# whypod.net
KiCad netlist of a schematic drawn in EAGLE
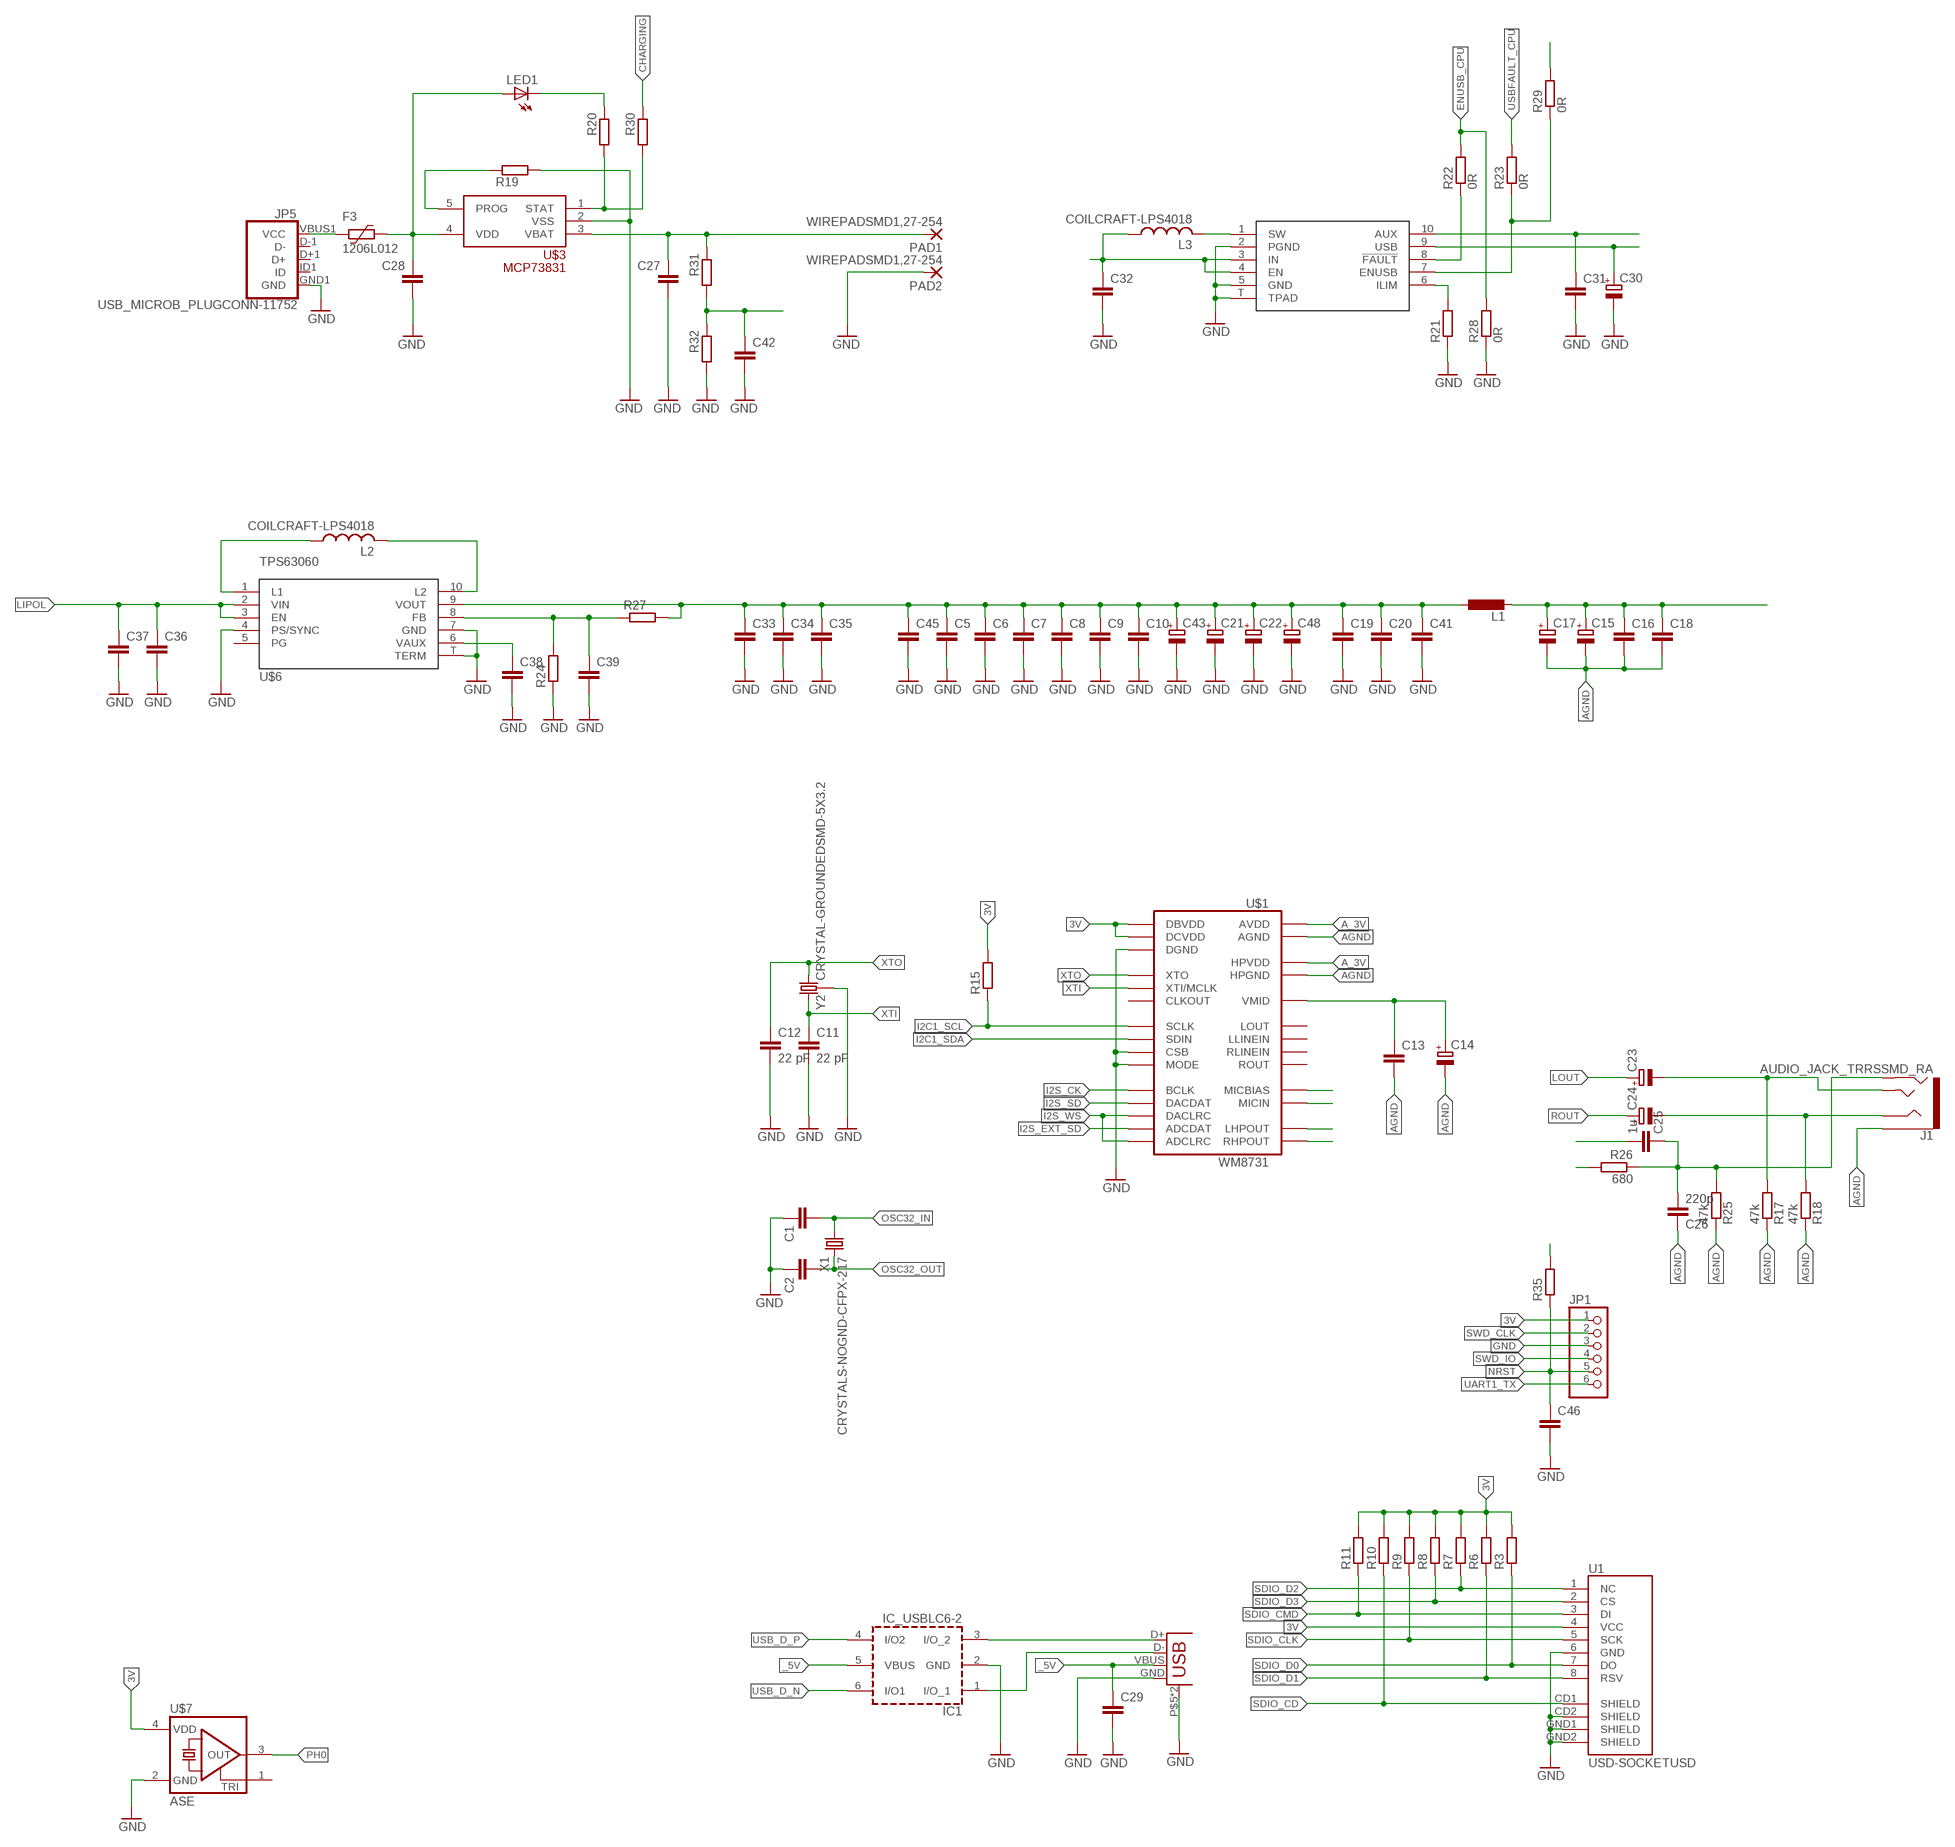
[diagram p0: schematic, sheet 1, part 1 of 2]
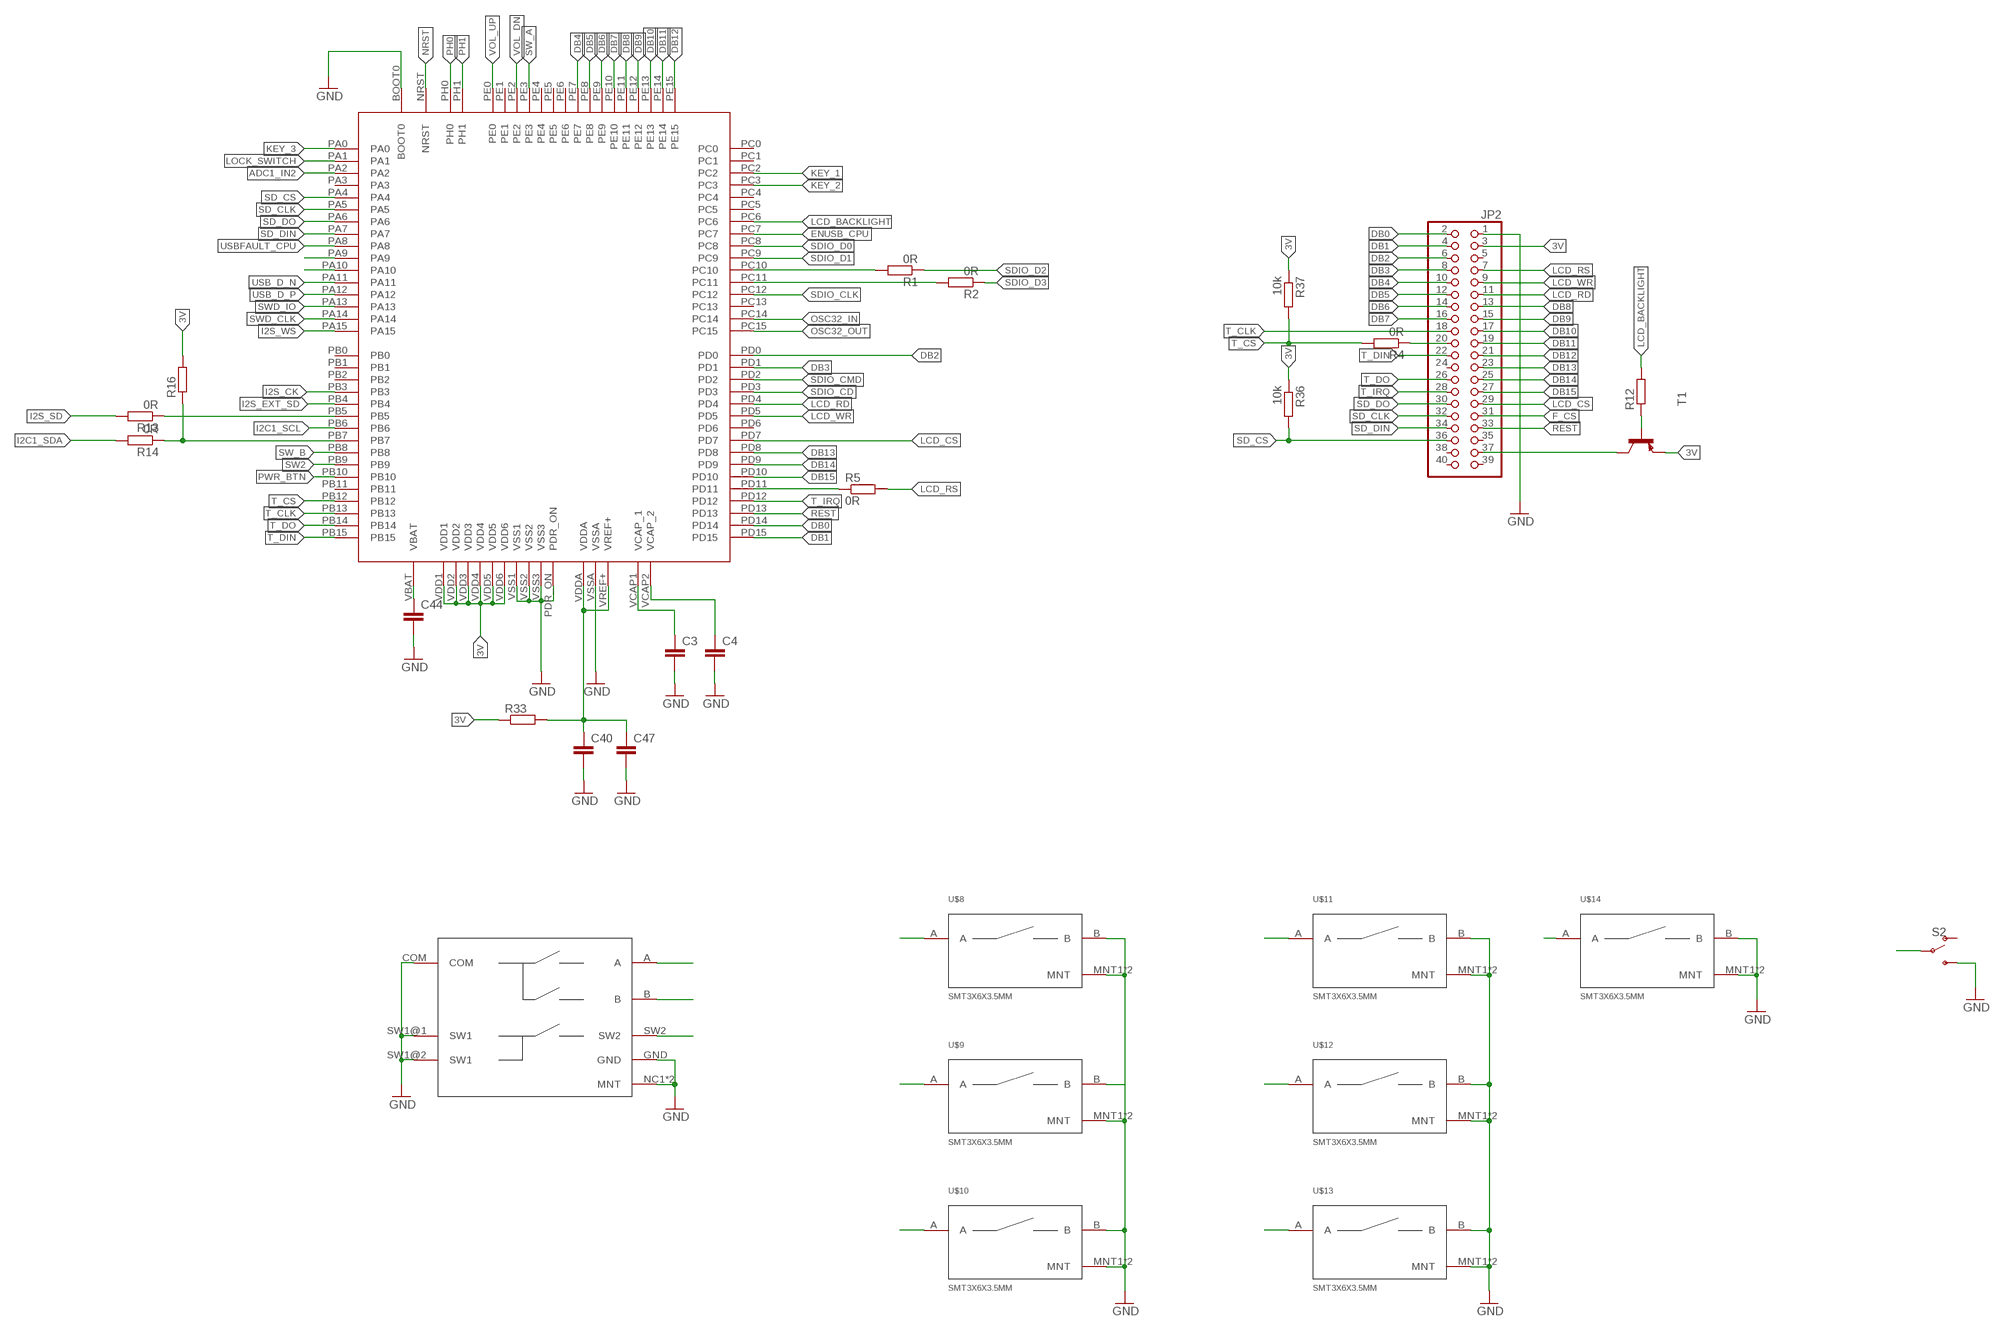
[diagram p1: schematic, sheet 1, part 2 of 2]

(export (version "E")
  (design (tool "Eeschema 10.0.6"))
  (components
    (comp (ref "C1")
      (value "C-EUC0603")
      (footprint "eagle-import:C0603")
      (libsource (lib "eagle-import") (part "C-EUC0603"))
    )
    (comp (ref "C2")
      (value "C-EUC0603")
      (footprint "eagle-import:C0603")
      (libsource (lib "eagle-import") (part "C-EUC0603"))
    )
    (comp (ref "C3")
      (value "C-EUC0603")
      (footprint "eagle-import:C0603")
      (libsource (lib "eagle-import") (part "C-EUC0603"))
    )
    (comp (ref "C4")
      (value "C-EUC0603")
      (footprint "eagle-import:C0603")
      (libsource (lib "eagle-import") (part "C-EUC0603"))
    )
    (comp (ref "C5")
      (value "C-EUC0603")
      (footprint "eagle-import:C0603")
      (libsource (lib "eagle-import") (part "C-EUC0603"))
    )
    (comp (ref "C6")
      (value "C-EUC0603")
      (footprint "eagle-import:C0603")
      (libsource (lib "eagle-import") (part "C-EUC0603"))
    )
    (comp (ref "C7")
      (value "C-EUC0402")
      (footprint "eagle-import:C0402")
      (libsource (lib "eagle-import") (part "C-EUC0402"))
    )
    (comp (ref "C8")
      (value "C-EUC0603")
      (footprint "eagle-import:C0603")
      (libsource (lib "eagle-import") (part "C-EUC0603"))
    )
    (comp (ref "C9")
      (value "C-EUC0603")
      (footprint "eagle-import:C0603")
      (libsource (lib "eagle-import") (part "C-EUC0603"))
    )
    (comp (ref "C10")
      (value "C-EUC0603")
      (footprint "eagle-import:C0603")
      (libsource (lib "eagle-import") (part "C-EUC0603"))
    )
    (comp (ref "C11")
      (value "22 pF")
      (footprint "eagle-import:C0603")
      (libsource (lib "eagle-import") (part "C-EUC0603"))
    )
    (comp (ref "C12")
      (value "22 pF")
      (footprint "eagle-import:C0603")
      (libsource (lib "eagle-import") (part "C-EUC0603"))
    )
    (comp (ref "C13")
      (value "C-EUC0603")
      (footprint "eagle-import:C0603")
      (libsource (lib "eagle-import") (part "C-EUC0603"))
    )
    (comp (ref "C14")
      (value "CPOL-EUSMCA")
      (footprint "eagle-import:SMC_A")
      (libsource (lib "eagle-import") (part "CPOL-EUSMCA"))
    )
    (comp (ref "C15")
      (value "CPOL-EUSMCA")
      (footprint "eagle-import:SMC_A")
      (libsource (lib "eagle-import") (part "CPOL-EUSMCA"))
    )
    (comp (ref "C16")
      (value "C-EUC0603")
      (footprint "eagle-import:C0603")
      (libsource (lib "eagle-import") (part "C-EUC0603"))
    )
    (comp (ref "C17")
      (value "CPOL-EUSMCA")
      (footprint "eagle-import:SMC_A")
      (libsource (lib "eagle-import") (part "CPOL-EUSMCA"))
    )
    (comp (ref "C18")
      (value "C-EUC0603")
      (footprint "eagle-import:C0603")
      (libsource (lib "eagle-import") (part "C-EUC0603"))
    )
    (comp (ref "C19")
      (value "C-EUC0603")
      (footprint "eagle-import:C0603")
      (libsource (lib "eagle-import") (part "C-EUC0603"))
    )
    (comp (ref "C20")
      (value "C-EUC0603")
      (footprint "eagle-import:C0603")
      (libsource (lib "eagle-import") (part "C-EUC0603"))
    )
    (comp (ref "C21")
      (value "CPOL-EUSMCA")
      (footprint "eagle-import:SMC_A")
      (libsource (lib "eagle-import") (part "CPOL-EUSMCA"))
    )
    (comp (ref "C22")
      (value "CPOL-EUSMCA")
      (footprint "eagle-import:SMC_A")
      (libsource (lib "eagle-import") (part "CPOL-EUSMCA"))
    )
    (comp (ref "C23")
      (value "CPOL-EUSMCE")
      (footprint "eagle-import:SMC_E")
      (libsource (lib "eagle-import") (part "CPOL-EUSMCE"))
    )
    (comp (ref "C24")
      (value "CPOL-EUSMCE")
      (footprint "eagle-import:SMC_E")
      (libsource (lib "eagle-import") (part "CPOL-EUSMCE"))
    )
    (comp (ref "C25")
      (value "1u")
      (footprint "eagle-import:C0603")
      (libsource (lib "eagle-import") (part "C-EUC0603"))
    )
    (comp (ref "C26")
      (value "220p")
      (footprint "eagle-import:C0603")
      (libsource (lib "eagle-import") (part "C-EUC0603"))
    )
    (comp (ref "C27")
      (value "C-EUC0603")
      (footprint "eagle-import:C0603")
      (libsource (lib "eagle-import") (part "C-EUC0603"))
    )
    (comp (ref "C28")
      (value "C-EUC0603")
      (footprint "eagle-import:C0603")
      (libsource (lib "eagle-import") (part "C-EUC0603"))
    )
    (comp (ref "C29")
      (value "C-EUC0603")
      (footprint "eagle-import:C0603")
      (libsource (lib "eagle-import") (part "C-EUC0603"))
    )
    (comp (ref "C30")
      (value "CPOL-EUSMCD")
      (footprint "eagle-import:SMC_D")
      (libsource (lib "eagle-import") (part "CPOL-EUSMCD"))
    )
    (comp (ref "C31")
      (value "C-EUC0603")
      (footprint "eagle-import:C0603")
      (libsource (lib "eagle-import") (part "C-EUC0603"))
    )
    (comp (ref "C32")
      (value "C-EUC0603")
      (footprint "eagle-import:C0603")
      (libsource (lib "eagle-import") (part "C-EUC0603"))
    )
    (comp (ref "C33")
      (value "C-EUC0805")
      (footprint "eagle-import:C0805")
      (libsource (lib "eagle-import") (part "C-EUC0805"))
    )
    (comp (ref "C34")
      (value "C-EUC0805")
      (footprint "eagle-import:C0805")
      (libsource (lib "eagle-import") (part "C-EUC0805"))
    )
    (comp (ref "C35")
      (value "C-EUC0805")
      (footprint "eagle-import:C0805")
      (libsource (lib "eagle-import") (part "C-EUC0805"))
    )
    (comp (ref "C36")
      (value "C-EUC0805")
      (footprint "eagle-import:C0805")
      (libsource (lib "eagle-import") (part "C-EUC0805"))
    )
    (comp (ref "C37")
      (value "C-EUC0805")
      (footprint "eagle-import:C0805")
      (libsource (lib "eagle-import") (part "C-EUC0805"))
    )
    (comp (ref "C38")
      (value "C-EUC0603")
      (footprint "eagle-import:C0603")
      (libsource (lib "eagle-import") (part "C-EUC0603"))
    )
    (comp (ref "C39")
      (value "C-EUC0402")
      (footprint "eagle-import:C0402")
      (libsource (lib "eagle-import") (part "C-EUC0402"))
    )
    (comp (ref "C40")
      (value "C-EUC0402")
      (footprint "eagle-import:C0402")
      (libsource (lib "eagle-import") (part "C-EUC0402"))
    )
    (comp (ref "C41")
      (value "C-EUC0402")
      (footprint "eagle-import:C0402")
      (libsource (lib "eagle-import") (part "C-EUC0402"))
    )
    (comp (ref "C42")
      (value "C-EUC0603")
      (footprint "eagle-import:C0603")
      (libsource (lib "eagle-import") (part "C-EUC0603"))
    )
    (comp (ref "C43")
      (value "CPOL-EUSMCA")
      (footprint "eagle-import:SMC_A")
      (libsource (lib "eagle-import") (part "CPOL-EUSMCA"))
    )
    (comp (ref "C44")
      (value "C-EUC0402")
      (footprint "eagle-import:C0402")
      (libsource (lib "eagle-import") (part "C-EUC0402"))
    )
    (comp (ref "C45")
      (value "C-EUC0402")
      (footprint "eagle-import:C0402")
      (libsource (lib "eagle-import") (part "C-EUC0402"))
    )
    (comp (ref "C46")
      (value "C-EUC0603")
      (footprint "eagle-import:C0603")
      (libsource (lib "eagle-import") (part "C-EUC0603"))
    )
    (comp (ref "C47")
      (value "C-EUC0603")
      (footprint "eagle-import:C0603")
      (libsource (lib "eagle-import") (part "C-EUC0603"))
    )
    (comp (ref "C48")
      (value "CPOL-EUSMCA")
      (footprint "eagle-import:SMC_A")
      (libsource (lib "eagle-import") (part "CPOL-EUSMCA"))
    )
    (comp (ref "F3")
      (value "1206L012")
      (footprint "eagle-import:1206L")
      (fields (field (name "MF") "Littelfuse"))
      (libsource (lib "eagle-import") (part "?1206L012"))
    )
    (comp (ref "IC1")
      (value "IC_USBLC6-2")
      (footprint "eagle-import:SOT-23-6L")
      (libsource (lib "eagle-import") (part "IC_USBLC6-2"))
    )
    (comp (ref "J1")
      (value "AUDIO_JACK_TRRSSMD_RA")
      (footprint "eagle-import:AUDIO_JACK_3.5MM_TRRS_SMD_RA")
      (libsource (lib "eagle-import") (part "AUDIO_JACK_TRRSSMD_RA"))
    )
    (comp (ref "JP1")
      (value "PINHD-1X06_2.54-SMD-90°")
      (footprint "eagle-import:1X06SMD_90")
      (libsource (lib "eagle-import") (part "PINHD-1X06_2.54-SMD-90°"))
    )
    (comp (ref "JP2")
      (value "PINHD-2X20_2.54-SMD")
      (footprint "eagle-import:2X20SMD")
      (libsource (lib "eagle-import") (part "PINHD-2X20_2.54-SMD"))
    )
    (comp (ref "JP5")
      (value "USB_MICROB_PLUGCONN-11752")
      (footprint "eagle-import:USB-B-MICRO-SMD_V03")
      (libsource (lib "eagle-import") (part "USB_MICROB_PLUGCONN-11752"))
    )
    (comp (ref "L1")
      (value "L-EUL3225M")
      (footprint "eagle-import:L3225M")
      (libsource (lib "eagle-import") (part "L-EUL3225M"))
    )
    (comp (ref "L2")
      (value "COILCRAFT-LPS4018")
      (footprint "eagle-import:LPS4018")
      (libsource (lib "eagle-import") (part "COILCRAFT-LPS4018"))
    )
    (comp (ref "L3")
      (value "COILCRAFT-LPS4018")
      (footprint "eagle-import:LPS4018")
      (libsource (lib "eagle-import") (part "COILCRAFT-LPS4018"))
    )
    (comp (ref "LED1")
      (value "LEDCHIP-LED0603")
      (footprint "eagle-import:CHIP-LED0603")
      (libsource (lib "eagle-import") (part "LEDCHIP-LED0603"))
    )
    (comp (ref "PAD1")
      (value "WIREPADSMD1,27-254")
      (footprint "eagle-import:SMD1,27-2,54")
      (libsource (lib "eagle-import") (part "WIREPADSMD1,27-254"))
    )
    (comp (ref "PAD2")
      (value "WIREPADSMD1,27-254")
      (footprint "eagle-import:SMD1,27-2,54")
      (libsource (lib "eagle-import") (part "WIREPADSMD1,27-254"))
    )
    (comp (ref "R1")
      (value "0R")
      (footprint "eagle-import:R0603")
      (libsource (lib "eagle-import") (part "R-EU_R0603"))
    )
    (comp (ref "R2")
      (value "0R")
      (footprint "eagle-import:R0603")
      (libsource (lib "eagle-import") (part "R-EU_R0603"))
    )
    (comp (ref "R3")
      (value "R-EU_R0603")
      (footprint "eagle-import:R0603")
      (libsource (lib "eagle-import") (part "R-EU_R0603"))
    )
    (comp (ref "R4")
      (value "0R")
      (footprint "eagle-import:R0603")
      (libsource (lib "eagle-import") (part "R-EU_R0603"))
    )
    (comp (ref "R5")
      (value "0R")
      (footprint "eagle-import:R0603")
      (libsource (lib "eagle-import") (part "R-EU_R0603"))
    )
    (comp (ref "R6")
      (value "R-EU_R0603")
      (footprint "eagle-import:R0603")
      (libsource (lib "eagle-import") (part "R-EU_R0603"))
    )
    (comp (ref "R7")
      (value "R-EU_R0402")
      (footprint "eagle-import:R0402")
      (libsource (lib "eagle-import") (part "R-EU_R0402"))
    )
    (comp (ref "R8")
      (value "R-EU_R0603")
      (footprint "eagle-import:R0603")
      (libsource (lib "eagle-import") (part "R-EU_R0603"))
    )
    (comp (ref "R9")
      (value "R-EU_R0402")
      (footprint "eagle-import:R0402")
      (libsource (lib "eagle-import") (part "R-EU_R0402"))
    )
    (comp (ref "R10")
      (value "R-EU_R0603")
      (footprint "eagle-import:R0603")
      (libsource (lib "eagle-import") (part "R-EU_R0603"))
    )
    (comp (ref "R11")
      (value "R-EU_R0603")
      (footprint "eagle-import:R0603")
      (libsource (lib "eagle-import") (part "R-EU_R0603"))
    )
    (comp (ref "R12")
      (value "R-EU_R0402")
      (footprint "eagle-import:R0402")
      (libsource (lib "eagle-import") (part "R-EU_R0402"))
    )
    (comp (ref "R13")
      (value "0R")
      (footprint "eagle-import:R0603")
      (libsource (lib "eagle-import") (part "R-EU_R0603"))
    )
    (comp (ref "R14")
      (value "0R")
      (footprint "eagle-import:R0603")
      (libsource (lib "eagle-import") (part "R-EU_R0603"))
    )
    (comp (ref "R15")
      (value "R-EU_R0603")
      (footprint "eagle-import:R0603")
      (libsource (lib "eagle-import") (part "R-EU_R0603"))
    )
    (comp (ref "R16")
      (value "R-EU_R0402")
      (footprint "eagle-import:R0402")
      (libsource (lib "eagle-import") (part "R-EU_R0402"))
    )
    (comp (ref "R17")
      (value "47k")
      (footprint "eagle-import:R0603")
      (libsource (lib "eagle-import") (part "R-EU_R0603"))
    )
    (comp (ref "R18")
      (value "47k")
      (footprint "eagle-import:R0603")
      (libsource (lib "eagle-import") (part "R-EU_R0603"))
    )
    (comp (ref "R19")
      (value "R-EU_R0603")
      (footprint "eagle-import:R0603")
      (libsource (lib "eagle-import") (part "R-EU_R0603"))
    )
    (comp (ref "R20")
      (value "R-EU_R0603")
      (footprint "eagle-import:R0603")
      (libsource (lib "eagle-import") (part "R-EU_R0603"))
    )
    (comp (ref "R21")
      (value "R-EU_R0603")
      (footprint "eagle-import:R0603")
      (libsource (lib "eagle-import") (part "R-EU_R0603"))
    )
    (comp (ref "R22")
      (value "0R")
      (footprint "eagle-import:R0603")
      (libsource (lib "eagle-import") (part "R-EU_R0603"))
    )
    (comp (ref "R23")
      (value "0R")
      (footprint "eagle-import:R0603")
      (libsource (lib "eagle-import") (part "R-EU_R0603"))
    )
    (comp (ref "R24")
      (value "R-EU_R0402")
      (footprint "eagle-import:R0402")
      (libsource (lib "eagle-import") (part "R-EU_R0402"))
    )
    (comp (ref "R25")
      (value "47k")
      (footprint "eagle-import:R0603")
      (libsource (lib "eagle-import") (part "R-EU_R0603"))
    )
    (comp (ref "R26")
      (value "680")
      (footprint "eagle-import:R0603")
      (libsource (lib "eagle-import") (part "R-EU_R0603"))
    )
    (comp (ref "R27")
      (value "R-EU_R0402")
      (footprint "eagle-import:R0402")
      (libsource (lib "eagle-import") (part "R-EU_R0402"))
    )
    (comp (ref "R28")
      (value "0R")
      (footprint "eagle-import:R0603")
      (libsource (lib "eagle-import") (part "R-EU_R0603"))
    )
    (comp (ref "R29")
      (value "0R")
      (footprint "eagle-import:R0603")
      (libsource (lib "eagle-import") (part "R-EU_R0603"))
    )
    (comp (ref "R30")
      (value "R-EU_R0603")
      (footprint "eagle-import:R0603")
      (libsource (lib "eagle-import") (part "R-EU_R0603"))
    )
    (comp (ref "R31")
      (value "R-EU_R0603")
      (footprint "eagle-import:R0603")
      (libsource (lib "eagle-import") (part "R-EU_R0603"))
    )
    (comp (ref "R32")
      (value "R-EU_R0603")
      (footprint "eagle-import:R0603")
      (libsource (lib "eagle-import") (part "R-EU_R0603"))
    )
    (comp (ref "R33")
      (value "R-EU_M0805")
      (footprint "eagle-import:M0805")
      (libsource (lib "eagle-import") (part "R-EU_M0805"))
    )
    (comp (ref "R35")
      (value "R-EU_R0603")
      (footprint "eagle-import:R0603")
      (libsource (lib "eagle-import") (part "R-EU_R0603"))
    )
    (comp (ref "R36")
      (value "10k")
      (footprint "eagle-import:R0603")
      (libsource (lib "eagle-import") (part "R-EU_R0603"))
    )
    (comp (ref "R37")
      (value "10k")
      (footprint "eagle-import:R0603")
      (libsource (lib "eagle-import") (part "R-EU_R0603"))
    )
    (comp (ref "S2")
      (value "SWITCH-SPDT-SMD-RIGHT-ANGLE")
      (footprint "eagle-import:SWITCH_SPST_SMD_A")
      (libsource (lib "eagle-import") (part "SWITCH-SPDT-SMD-RIGHT-ANGLE"))
    )
    (comp (ref "T1")
      (value "BC857A-PNP-SOT23-BEC")
      (footprint "eagle-import:SOT23-BEC")
      (libsource (lib "eagle-import") (part "-PNP-SOT23-BECBC857A"))
    )
    (comp (ref "U$1")
      (value "WM8731")
      (footprint "eagle-import:28-SSOP")
      (libsource (lib "eagle-import") (part "WM8731"))
    )
    (comp (ref "U$2")
      (value "STM32F4V_100PIN_GENERIC")
      (footprint "eagle-import:LQFP100")
      (libsource (lib "eagle-import") (part "STM32F4V_100PIN_GENERIC"))
    )
    (comp (ref "U$3")
      (value "MCP73831SOT-23-5")
      (footprint "eagle-import:SOT-23-5")
      (libsource (lib "eagle-import") (part "MCP73831SOT-23-5"))
    )
    (comp (ref "U$4")
      (value "EVQWKSMD")
      (footprint "eagle-import:EVQWK_SMD")
      (libsource (lib "eagle-import") (part "EVQWKSMD"))
    )
    (comp (ref "U$5")
      (value "TPS2500")
      (footprint "eagle-import:DRC10")
      (libsource (lib "eagle-import") (part "TPS2500"))
    )
    (comp (ref "U$6")
      (value "TPS63060")
      (footprint "eagle-import:DRC10")
      (libsource (lib "eagle-import") (part "TPS63060"))
    )
    (comp (ref "U$7")
      (value "ASE")
      (footprint "eagle-import:ASE")
      (libsource (lib "eagle-import") (part "ASE"))
    )
    (comp (ref "U$8")
      (value "SMT3X6X3.5MM")
      (footprint "eagle-import:SMT3X6X3.5MM")
      (libsource (lib "eagle-import") (part "SMT3X6X3.5MM"))
    )
    (comp (ref "U$9")
      (value "SMT3X6X3.5MM")
      (footprint "eagle-import:SMT3X6X3.5MM")
      (libsource (lib "eagle-import") (part "SMT3X6X3.5MM"))
    )
    (comp (ref "U$10")
      (value "SMT3X6X3.5MM")
      (footprint "eagle-import:SMT3X6X3.5MM")
      (libsource (lib "eagle-import") (part "SMT3X6X3.5MM"))
    )
    (comp (ref "U$11")
      (value "SMT3X6X3.5MM")
      (footprint "eagle-import:SMT3X6X3.5MM")
      (libsource (lib "eagle-import") (part "SMT3X6X3.5MM"))
    )
    (comp (ref "U$12")
      (value "SMT3X6X3.5MM")
      (footprint "eagle-import:SMT3X6X3.5MM")
      (libsource (lib "eagle-import") (part "SMT3X6X3.5MM"))
    )
    (comp (ref "U$13")
      (value "SMT3X6X3.5MM")
      (footprint "eagle-import:SMT3X6X3.5MM")
      (libsource (lib "eagle-import") (part "SMT3X6X3.5MM"))
    )
    (comp (ref "U$14")
      (value "SMT3X6X3.5MM")
      (footprint "eagle-import:SMT3X6X3.5MM")
      (libsource (lib "eagle-import") (part "SMT3X6X3.5MM"))
    )
    (comp (ref "U1")
      (value "USD-SOCKETUSD")
      (footprint "eagle-import:USD-SOCKET-PP")
      (libsource (lib "eagle-import") (part "USD-SOCKETUSD"))
    )
    (comp (ref "X1")
      (value "CRYSTALS-NOGND-CFPX-217")
      (footprint "eagle-import:3.2X1.5-2-PAD")
      (libsource (lib "eagle-import") (part "CRYSTALS-NOGND-CFPX-217"))
    )
    (comp (ref "X2")
      (value "USB-A-S")
      (footprint "eagle-import:USB-A-S")
      (libsource (lib "eagle-import") (part "USB-A-S"))
    )
    (comp (ref "Y2")
      (value "CRYSTAL-GROUNDEDSMD-5X3.2")
      (footprint "eagle-import:CRYSTAL-SMD-5X3.2-4PAD")
      (libsource (lib "eagle-import") (part "CRYSTAL-GROUNDEDSMD-5X3.2"))
    )
  )
  (nets
    (net (code "1") (name "/MICBIAS") (class "Default")
      (node (ref "R26") (pin "2") (pinfunction "2_2") (pintype "passive"))
      (node (ref "U$1") (pin "P$17") (pinfunction "MICBIAS_P$17") (pintype "output"))
    )
    (net (code "2") (name "/MICIN") (class "Default")
      (node (ref "C25") (pin "2") (pinfunction "2_2") (pintype "passive"))
      (node (ref "U$1") (pin "P$18") (pinfunction "MICIN_P$18") (pintype "input"))
    )
    (net (code "3") (name "3V") (class "Default")
      (node (ref "C10") (pin "1") (pinfunction "1_1") (pintype "passive"))
      (node (ref "C19") (pin "1") (pinfunction "1_1") (pintype "passive"))
      (node (ref "C20") (pin "1") (pinfunction "1_1") (pintype "passive"))
      (node (ref "C21") (pin "+") (pinfunction "+_+") (pintype "passive"))
      (node (ref "C22") (pin "+") (pinfunction "+_+") (pintype "passive"))
      (node (ref "C33") (pin "1") (pinfunction "1_1") (pintype "passive"))
      (node (ref "C34") (pin "1") (pinfunction "1_1") (pintype "passive"))
      (node (ref "C35") (pin "1") (pinfunction "1_1") (pintype "passive"))
      (node (ref "C41") (pin "1") (pinfunction "1_1") (pintype "passive"))
      (node (ref "C43") (pin "+") (pinfunction "+_+") (pintype "passive"))
      (node (ref "C45") (pin "1") (pinfunction "1_1") (pintype "passive"))
      (node (ref "C48") (pin "+") (pinfunction "+_+") (pintype "passive"))
      (node (ref "C5") (pin "1") (pinfunction "1_1") (pintype "passive"))
      (node (ref "C6") (pin "1") (pinfunction "1_1") (pintype "passive"))
      (node (ref "C7") (pin "1") (pinfunction "1_1") (pintype "passive"))
      (node (ref "C8") (pin "1") (pinfunction "1_1") (pintype "passive"))
      (node (ref "C9") (pin "1") (pinfunction "1_1") (pintype "passive"))
      (node (ref "JP1") (pin "1") (pinfunction "1_1") (pintype "passive"))
      (node (ref "JP2") (pin "3") (pinfunction "3_3") (pintype "passive"))
      (node (ref "L1") (pin "1") (pinfunction "1_1") (pintype "passive"))
      (node (ref "R10") (pin "2") (pinfunction "2_2") (pintype "passive"))
      (node (ref "R11") (pin "2") (pinfunction "2_2") (pintype "passive"))
      (node (ref "R15") (pin "2") (pinfunction "2_2") (pintype "passive"))
      (node (ref "R16") (pin "2") (pinfunction "2_2") (pintype "passive"))
      (node (ref "R27") (pin "2") (pinfunction "2_2") (pintype "passive"))
      (node (ref "R29") (pin "2") (pinfunction "2_2") (pintype "passive"))
      (node (ref "R3") (pin "2") (pinfunction "2_2") (pintype "passive"))
      (node (ref "R33") (pin "1") (pinfunction "1_1") (pintype "passive"))
      (node (ref "R35") (pin "2") (pinfunction "2_2") (pintype "passive"))
      (node (ref "R36") (pin "1") (pinfunction "1_1") (pintype "passive"))
      (node (ref "R37") (pin "1") (pinfunction "1_1") (pintype "passive"))
      (node (ref "R6") (pin "2") (pinfunction "2_2") (pintype "passive"))
      (node (ref "R7") (pin "2") (pinfunction "2_2") (pintype "passive"))
      (node (ref "R8") (pin "2") (pinfunction "2_2") (pintype "passive"))
      (node (ref "R9") (pin "2") (pinfunction "2_2") (pintype "passive"))
      (node (ref "T1") (pin "E") (pinfunction "E_E") (pintype "passive"))
      (node (ref "U$1") (pin "P$1") (pinfunction "DBVDD_P$1") (pintype "power_in"))
      (node (ref "U$1") (pin "P$27") (pinfunction "DCVDD_P$27") (pintype "power_in"))
      (node (ref "U$2") (pin "VDD1") (pinfunction "VDD1_VDD1") (pintype "bidirectional"))
      (node (ref "U$2") (pin "VDD2") (pinfunction "VDD2_VDD2") (pintype "bidirectional"))
      (node (ref "U$2") (pin "VDD3") (pinfunction "VDD3_VDD3") (pintype "bidirectional"))
      (node (ref "U$2") (pin "VDD4") (pinfunction "VDD4_VDD4") (pintype "bidirectional"))
      (node (ref "U$2") (pin "VDD5") (pinfunction "VDD5_VDD5") (pintype "bidirectional"))
      (node (ref "U$2") (pin "VDD6") (pinfunction "VDD6_VDD6") (pintype "bidirectional"))
      (node (ref "U$6") (pin "9") (pinfunction "VOUT_9") (pintype "bidirectional"))
      (node (ref "U$7") (pin "4") (pinfunction "VDD_4") (pintype "power_in"))
      (node (ref "U1") (pin "4") (pinfunction "VCC_4") (pintype "bidirectional"))
    )
    (net (code "4") (name "ADC1_IN2") (class "Default")
      (node (ref "C42") (pin "1") (pinfunction "1_1") (pintype "passive"))
      (node (ref "R31") (pin "2") (pinfunction "2_2") (pintype "passive"))
      (node (ref "R32") (pin "1") (pinfunction "1_1") (pintype "passive"))
      (node (ref "U$2") (pin "PA2") (pinfunction "PA2_PA2") (pintype "bidirectional"))
    )
    (net (code "5") (name "AGND") (class "Default")
      (node (ref "C13") (pin "2") (pinfunction "2_2") (pintype "passive"))
      (node (ref "C14") (pin "-") (pinfunction "-_-") (pintype "passive"))
      (node (ref "C15") (pin "-") (pinfunction "-_-") (pintype "passive"))
      (node (ref "C16") (pin "2") (pinfunction "2_2") (pintype "passive"))
      (node (ref "C17") (pin "-") (pinfunction "-_-") (pintype "passive"))
      (node (ref "C18") (pin "2") (pinfunction "2_2") (pintype "passive"))
      (node (ref "C26") (pin "1") (pinfunction "1_1") (pintype "passive"))
      (node (ref "J1") (pin "EARTH") (pinfunction "EARTH_EARTH") (pintype "bidirectional"))
      (node (ref "R17") (pin "1") (pinfunction "1_1") (pintype "passive"))
      (node (ref "R18") (pin "1") (pinfunction "1_1") (pintype "passive"))
      (node (ref "R25") (pin "1") (pinfunction "1_1") (pintype "passive"))
      (node (ref "U$1") (pin "P$11") (pinfunction "HPGND_P$11") (pintype "power_in"))
      (node (ref "U$1") (pin "P$15") (pinfunction "AGND_P$15") (pintype "power_in"))
    )
    (net (code "6") (name "A_3V") (class "Default")
      (node (ref "C15") (pin "+") (pinfunction "+_+") (pintype "passive"))
      (node (ref "C16") (pin "1") (pinfunction "1_1") (pintype "passive"))
      (node (ref "C17") (pin "+") (pinfunction "+_+") (pintype "passive"))
      (node (ref "C18") (pin "1") (pinfunction "1_1") (pintype "passive"))
      (node (ref "L1") (pin "2") (pinfunction "2_2") (pintype "passive"))
      (node (ref "U$1") (pin "P$14") (pinfunction "AVDD_P$14") (pintype "power_in"))
      (node (ref "U$1") (pin "P$8") (pinfunction "HPVDD_P$8") (pintype "power_in"))
    )
    (net (code "7") (name "CHARGING") (class "Default")
      (node (ref "R30") (pin "1") (pinfunction "1_1") (pintype "passive"))
      (node (ref "U$2") (pin "PA10") (pinfunction "PA10_PA10") (pintype "bidirectional"))
    )
    (net (code "8") (name "DB0") (class "Default")
      (node (ref "JP2") (pin "2") (pinfunction "2_2") (pintype "passive"))
      (node (ref "U$2") (pin "PD14") (pinfunction "PD14_PD14") (pintype "bidirectional"))
    )
    (net (code "9") (name "DB1") (class "Default")
      (node (ref "JP2") (pin "4") (pinfunction "4_4") (pintype "passive"))
      (node (ref "U$2") (pin "PD15") (pinfunction "PD15_PD15") (pintype "bidirectional"))
    )
    (net (code "10") (name "DB2") (class "Default")
      (node (ref "JP2") (pin "6") (pinfunction "6_6") (pintype "passive"))
      (node (ref "U$2") (pin "PD0") (pinfunction "PD0_PD0") (pintype "bidirectional"))
    )
    (net (code "11") (name "DB3") (class "Default")
      (node (ref "JP2") (pin "8") (pinfunction "8_8") (pintype "passive"))
      (node (ref "U$2") (pin "PD1") (pinfunction "PD1_PD1") (pintype "bidirectional"))
    )
    (net (code "12") (name "DB4") (class "Default")
      (node (ref "JP2") (pin "10") (pinfunction "10_10") (pintype "passive"))
      (node (ref "U$2") (pin "PE7") (pinfunction "PE7_PE7") (pintype "bidirectional"))
    )
    (net (code "13") (name "DB5") (class "Default")
      (node (ref "JP2") (pin "12") (pinfunction "12_12") (pintype "passive"))
      (node (ref "U$2") (pin "PE8") (pinfunction "PE8_PE8") (pintype "bidirectional"))
    )
    (net (code "14") (name "DB6") (class "Default")
      (node (ref "JP2") (pin "14") (pinfunction "14_14") (pintype "passive"))
      (node (ref "U$2") (pin "PE9") (pinfunction "PE9_PE9") (pintype "bidirectional"))
    )
    (net (code "15") (name "DB7") (class "Default")
      (node (ref "JP2") (pin "16") (pinfunction "16_16") (pintype "passive"))
      (node (ref "U$2") (pin "PE10") (pinfunction "PE10_PE10") (pintype "bidirectional"))
    )
    (net (code "16") (name "DB8") (class "Default")
      (node (ref "JP2") (pin "13") (pinfunction "13_13") (pintype "passive"))
      (node (ref "U$2") (pin "PE11") (pinfunction "PE11_PE11") (pintype "bidirectional"))
    )
    (net (code "17") (name "DB9") (class "Default")
      (node (ref "JP2") (pin "15") (pinfunction "15_15") (pintype "passive"))
      (node (ref "U$2") (pin "PE12") (pinfunction "PE12_PE12") (pintype "bidirectional"))
    )
    (net (code "18") (name "DB10") (class "Default")
      (node (ref "JP2") (pin "17") (pinfunction "17_17") (pintype "passive"))
      (node (ref "U$2") (pin "PE13") (pinfunction "PE13_PE13") (pintype "bidirectional"))
    )
    (net (code "19") (name "DB11") (class "Default")
      (node (ref "JP2") (pin "19") (pinfunction "19_19") (pintype "passive"))
      (node (ref "U$2") (pin "PE14") (pinfunction "PE14_PE14") (pintype "bidirectional"))
    )
    (net (code "20") (name "DB12") (class "Default")
      (node (ref "JP2") (pin "21") (pinfunction "21_21") (pintype "passive"))
      (node (ref "U$2") (pin "PE15") (pinfunction "PE15_PE15") (pintype "bidirectional"))
    )
    (net (code "21") (name "DB13") (class "Default")
      (node (ref "JP2") (pin "23") (pinfunction "23_23") (pintype "passive"))
      (node (ref "U$2") (pin "PD8") (pinfunction "PD8_PD8") (pintype "bidirectional"))
    )
    (net (code "22") (name "DB14") (class "Default")
      (node (ref "JP2") (pin "25") (pinfunction "25_25") (pintype "passive"))
      (node (ref "U$2") (pin "PD9") (pinfunction "PD9_PD9") (pintype "bidirectional"))
    )
    (net (code "23") (name "DB15") (class "Default")
      (node (ref "JP2") (pin "27") (pinfunction "27_27") (pintype "passive"))
      (node (ref "U$2") (pin "PD10") (pinfunction "PD10_PD10") (pintype "bidirectional"))
    )
    (net (code "24") (name "ENUSB_CPU") (class "Default")
      (node (ref "R22") (pin "2") (pinfunction "2_2") (pintype "passive"))
      (node (ref "R28") (pin "2") (pinfunction "2_2") (pintype "passive"))
      (node (ref "U$2") (pin "PC7") (pinfunction "PC7_PC7") (pintype "bidirectional"))
    )
    (net (code "25") (name "F_CS") (class "Default")
      (node (ref "JP2") (pin "31") (pinfunction "31_31") (pintype "passive"))
    )
    (net (code "26") (name "GND") (class "Default")
      (node (ref "C1") (pin "1") (pinfunction "1_1") (pintype "passive"))
      (node (ref "C10") (pin "2") (pinfunction "2_2") (pintype "passive"))
      (node (ref "C11") (pin "2") (pinfunction "2_2") (pintype "passive"))
      (node (ref "C12") (pin "2") (pinfunction "2_2") (pintype "passive"))
      (node (ref "C19") (pin "2") (pinfunction "2_2") (pintype "passive"))
      (node (ref "C2") (pin "1") (pinfunction "1_1") (pintype "passive"))
      (node (ref "C20") (pin "2") (pinfunction "2_2") (pintype "passive"))
      (node (ref "C21") (pin "-") (pinfunction "-_-") (pintype "passive"))
      (node (ref "C22") (pin "-") (pinfunction "-_-") (pintype "passive"))
      (node (ref "C27") (pin "2") (pinfunction "2_2") (pintype "passive"))
      (node (ref "C28") (pin "2") (pinfunction "2_2") (pintype "passive"))
      (node (ref "C29") (pin "2") (pinfunction "2_2") (pintype "passive"))
      (node (ref "C3") (pin "2") (pinfunction "2_2") (pintype "passive"))
      (node (ref "C30") (pin "-") (pinfunction "-_-") (pintype "passive"))
      (node (ref "C31") (pin "2") (pinfunction "2_2") (pintype "passive"))
      (node (ref "C32") (pin "2") (pinfunction "2_2") (pintype "passive"))
      (node (ref "C33") (pin "2") (pinfunction "2_2") (pintype "passive"))
      (node (ref "C34") (pin "2") (pinfunction "2_2") (pintype "passive"))
      (node (ref "C35") (pin "2") (pinfunction "2_2") (pintype "passive"))
      (node (ref "C36") (pin "2") (pinfunction "2_2") (pintype "passive"))
      (node (ref "C37") (pin "2") (pinfunction "2_2") (pintype "passive"))
      (node (ref "C38") (pin "2") (pinfunction "2_2") (pintype "passive"))
      (node (ref "C39") (pin "2") (pinfunction "2_2") (pintype "passive"))
      (node (ref "C4") (pin "2") (pinfunction "2_2") (pintype "passive"))
      (node (ref "C40") (pin "2") (pinfunction "2_2") (pintype "passive"))
      (node (ref "C41") (pin "2") (pinfunction "2_2") (pintype "passive"))
      (node (ref "C42") (pin "2") (pinfunction "2_2") (pintype "passive"))
      (node (ref "C43") (pin "-") (pinfunction "-_-") (pintype "passive"))
      (node (ref "C44") (pin "2") (pinfunction "2_2") (pintype "passive"))
      (node (ref "C45") (pin "2") (pinfunction "2_2") (pintype "passive"))
      (node (ref "C46") (pin "2") (pinfunction "2_2") (pintype "passive"))
      (node (ref "C47") (pin "2") (pinfunction "2_2") (pintype "passive"))
      (node (ref "C48") (pin "-") (pinfunction "-_-") (pintype "passive"))
      (node (ref "C5") (pin "2") (pinfunction "2_2") (pintype "passive"))
      (node (ref "C6") (pin "2") (pinfunction "2_2") (pintype "passive"))
      (node (ref "C7") (pin "2") (pinfunction "2_2") (pintype "passive"))
      (node (ref "C8") (pin "2") (pinfunction "2_2") (pintype "passive"))
      (node (ref "C9") (pin "2") (pinfunction "2_2") (pintype "passive"))
      (node (ref "IC1") (pin "2") (pinfunction "GND_2") (pintype "bidirectional"))
      (node (ref "JP1") (pin "3") (pinfunction "3_3") (pintype "passive"))
      (node (ref "JP2") (pin "1") (pinfunction "1_1") (pintype "passive"))
      (node (ref "JP5") (pin "GND1") (pinfunction "GND_GND1") (pintype "bidirectional"))
      (node (ref "PAD2") (pin "1") (pinfunction "P_1") (pintype "passive"))
      (node (ref "R19") (pin "2") (pinfunction "2_2") (pintype "passive"))
      (node (ref "R21") (pin "1") (pinfunction "1_1") (pintype "passive"))
      (node (ref "R24") (pin "1") (pinfunction "1_1") (pintype "passive"))
      (node (ref "R28") (pin "1") (pinfunction "1_1") (pintype "passive"))
      (node (ref "R32") (pin "2") (pinfunction "2_2") (pintype "passive"))
      (node (ref "S2") (pin "3") (pinfunction "S_3") (pintype "passive"))
      (node (ref "U$1") (pin "P$21") (pinfunction "MODE_P$21") (pintype "input"))
      (node (ref "U$1") (pin "P$22") (pinfunction "CSB_P$22") (pintype "input"))
      (node (ref "U$1") (pin "P$28") (pinfunction "DGND_P$28") (pintype "power_in"))
      (node (ref "U$10") (pin "B") (pinfunction "B_B") (pintype "bidirectional"))
      (node (ref "U$10") (pin "MNT1") (pinfunction "MNT_MNT1") (pintype "bidirectional"))
      (node (ref "U$10") (pin "MNT2") (pinfunction "MNT_MNT2") (pintype "bidirectional"))
      (node (ref "U$11") (pin "B") (pinfunction "B_B") (pintype "bidirectional"))
      (node (ref "U$11") (pin "MNT1") (pinfunction "MNT_MNT1") (pintype "bidirectional"))
      (node (ref "U$11") (pin "MNT2") (pinfunction "MNT_MNT2") (pintype "bidirectional"))
      (node (ref "U$12") (pin "B") (pinfunction "B_B") (pintype "bidirectional"))
      (node (ref "U$12") (pin "MNT1") (pinfunction "MNT_MNT1") (pintype "bidirectional"))
      (node (ref "U$12") (pin "MNT2") (pinfunction "MNT_MNT2") (pintype "bidirectional"))
      (node (ref "U$13") (pin "B") (pinfunction "B_B") (pintype "bidirectional"))
      (node (ref "U$13") (pin "MNT1") (pinfunction "MNT_MNT1") (pintype "bidirectional"))
      (node (ref "U$13") (pin "MNT2") (pinfunction "MNT_MNT2") (pintype "bidirectional"))
      (node (ref "U$14") (pin "B") (pinfunction "B_B") (pintype "bidirectional"))
      (node (ref "U$14") (pin "MNT1") (pinfunction "MNT_MNT1") (pintype "bidirectional"))
      (node (ref "U$14") (pin "MNT2") (pinfunction "MNT_MNT2") (pintype "bidirectional"))
      (node (ref "U$2") (pin "BOOT0") (pinfunction "BOOT0_BOOT0") (pintype "bidirectional"))
      (node (ref "U$2") (pin "PDR_ON") (pinfunction "PDR_ON_PDR_ON") (pintype "bidirectional"))
      (node (ref "U$2") (pin "VSS1") (pinfunction "VSS1_VSS1") (pintype "bidirectional"))
      (node (ref "U$2") (pin "VSS2") (pinfunction "VSS2_VSS2") (pintype "bidirectional"))
      (node (ref "U$2") (pin "VSS3") (pinfunction "VSS3_VSS3") (pintype "bidirectional"))
      (node (ref "U$2") (pin "VSSA") (pinfunction "VSSA_VSSA") (pintype "bidirectional"))
      (node (ref "U$3") (pin "2") (pinfunction "VSS_2") (pintype "bidirectional"))
      (node (ref "U$4") (pin "COM") (pinfunction "COM_COM") (pintype "bidirectional"))
      (node (ref "U$4") (pin "GND") (pinfunction "GND_GND") (pintype "bidirectional"))
      (node (ref "U$4") (pin "NC1") (pinfunction "MNT_NC1") (pintype "bidirectional"))
      (node (ref "U$4") (pin "NC2") (pinfunction "MNT_NC2") (pintype "bidirectional"))
      (node (ref "U$4") (pin "SW1@1") (pinfunction "SW1_SW1@1") (pintype "bidirectional"))
      (node (ref "U$4") (pin "SW1@2") (pinfunction "SW1_SW1@2") (pintype "bidirectional"))
      (node (ref "U$5") (pin "2") (pinfunction "PGND_2") (pintype "bidirectional"))
      (node (ref "U$5") (pin "5") (pinfunction "GND_5") (pintype "bidirectional"))
      (node (ref "U$5") (pin "T") (pinfunction "TPAD_T") (pintype "bidirectional"))
      (node (ref "U$6") (pin "4") (pinfunction "PS/SYNC_4") (pintype "bidirectional"))
      (node (ref "U$6") (pin "7") (pinfunction "GND_7") (pintype "bidirectional"))
      (node (ref "U$6") (pin "T") (pinfunction "TERM_T") (pintype "bidirectional"))
      (node (ref "U$7") (pin "2") (pinfunction "GND_2") (pintype "power_in"))
      (node (ref "U$8") (pin "B") (pinfunction "B_B") (pintype "bidirectional"))
      (node (ref "U$8") (pin "MNT1") (pinfunction "MNT_MNT1") (pintype "bidirectional"))
      (node (ref "U$8") (pin "MNT2") (pinfunction "MNT_MNT2") (pintype "bidirectional"))
      (node (ref "U$9") (pin "B") (pinfunction "B_B") (pintype "bidirectional"))
      (node (ref "U$9") (pin "MNT1") (pinfunction "MNT_MNT1") (pintype "bidirectional"))
      (node (ref "U$9") (pin "MNT2") (pinfunction "MNT_MNT2") (pintype "bidirectional"))
      (node (ref "U1") (pin "6") (pinfunction "GND_6") (pintype "bidirectional"))
      (node (ref "U1") (pin "CD2") (pinfunction "SHIELD_CD2") (pintype "bidirectional"))
      (node (ref "U1") (pin "GND1") (pinfunction "SHIELD_GND1") (pintype "bidirectional"))
      (node (ref "U1") (pin "GND2") (pinfunction "SHIELD_GND2") (pintype "bidirectional"))
      (node (ref "X2") (pin "GND") (pinfunction "GND_GND") (pintype "bidirectional"))
      (node (ref "X2") (pin "P$5") (pinfunction "SHIELD_P$5") (pintype "bidirectional"))
      (node (ref "X2") (pin "P$6") (pinfunction "SHIELD_P$6") (pintype "bidirectional"))
      (node (ref "Y2") (pin "2") (pinfunction "3_2") (pintype "passive"))
      (node (ref "Y2") (pin "4") (pinfunction "3_4") (pintype "passive"))
    )
    (net (code "27") (name "I2C1_SCL") (class "Default")
      (node (ref "R15") (pin "1") (pinfunction "1_1") (pintype "passive"))
      (node (ref "U$1") (pin "P$24") (pinfunction "SCLK_P$24") (pintype "input"))
      (node (ref "U$2") (pin "PB6") (pinfunction "PB6_PB6") (pintype "bidirectional"))
    )
    (net (code "28") (name "I2C1_SDA") (class "Default")
      (node (ref "R14") (pin "2") (pinfunction "2_2") (pintype "passive"))
      (node (ref "U$1") (pin "P$23") (pinfunction "SDIN_P$23") (pintype "bidirectional"))
    )
    (net (code "29") (name "I2S_CK") (class "Default")
      (node (ref "U$1") (pin "P$3") (pinfunction "BCLK_P$3") (pintype "bidirectional"))
      (node (ref "U$2") (pin "PB3") (pinfunction "PB3_PB3") (pintype "bidirectional"))
    )
    (net (code "30") (name "I2S_EXT_SD") (class "Default")
      (node (ref "U$1") (pin "P$6") (pinfunction "ADCDAT_P$6") (pintype "output"))
      (node (ref "U$2") (pin "PB4") (pinfunction "PB4_PB4") (pintype "bidirectional"))
    )
    (net (code "31") (name "I2S_SD") (class "Default")
      (node (ref "R13") (pin "2") (pinfunction "2_2") (pintype "passive"))
      (node (ref "U$1") (pin "P$4") (pinfunction "DACDAT_P$4") (pintype "input"))
    )
    (net (code "32") (name "I2S_WS") (class "Default")
      (node (ref "U$1") (pin "P$5") (pinfunction "DACLRC_P$5") (pintype "bidirectional"))
      (node (ref "U$1") (pin "P$7") (pinfunction "ADCLRC_P$7") (pintype "bidirectional"))
      (node (ref "U$2") (pin "PA15") (pinfunction "PA15_PA15") (pintype "bidirectional"))
    )
    (net (code "33") (name "KEY_1") (class "Default")
      (node (ref "U$11") (pin "A") (pinfunction "A_A") (pintype "bidirectional"))
      (node (ref "U$2") (pin "PC2") (pinfunction "PC2_PC2") (pintype "bidirectional"))
    )
    (net (code "34") (name "KEY_2") (class "Default")
      (node (ref "U$12") (pin "A") (pinfunction "A_A") (pintype "bidirectional"))
      (node (ref "U$2") (pin "PC3") (pinfunction "PC3_PC3") (pintype "bidirectional"))
    )
    (net (code "35") (name "KEY_3") (class "Default")
      (node (ref "U$13") (pin "A") (pinfunction "A_A") (pintype "bidirectional"))
      (node (ref "U$2") (pin "PA0") (pinfunction "PA0_PA0") (pintype "bidirectional"))
    )
    (net (code "36") (name "LCD_BACKLIGHT") (class "Default")
      (node (ref "R12") (pin "2") (pinfunction "2_2") (pintype "passive"))
      (node (ref "U$2") (pin "PC6") (pinfunction "PC6_PC6") (pintype "bidirectional"))
    )
    (net (code "37") (name "LCD_CS") (class "Default")
      (node (ref "JP2") (pin "29") (pinfunction "29_29") (pintype "passive"))
      (node (ref "U$2") (pin "PD7") (pinfunction "PD7_PD7") (pintype "bidirectional"))
    )
    (net (code "38") (name "LCD_RD") (class "Default")
      (node (ref "JP2") (pin "11") (pinfunction "11_11") (pintype "passive"))
      (node (ref "U$2") (pin "PD4") (pinfunction "PD4_PD4") (pintype "bidirectional"))
    )
    (net (code "39") (name "LCD_RS") (class "Default")
      (node (ref "JP2") (pin "7") (pinfunction "7_7") (pintype "passive"))
      (node (ref "R5") (pin "2") (pinfunction "2_2") (pintype "passive"))
    )
    (net (code "40") (name "LCD_WR") (class "Default")
      (node (ref "JP2") (pin "9") (pinfunction "9_9") (pintype "passive"))
      (node (ref "U$2") (pin "PD5") (pinfunction "PD5_PD5") (pintype "bidirectional"))
    )
    (net (code "41") (name "LIPOL") (class "Default")
      (node (ref "C27") (pin "1") (pinfunction "1_1") (pintype "passive"))
      (node (ref "C32") (pin "1") (pinfunction "1_1") (pintype "passive"))
      (node (ref "C36") (pin "1") (pinfunction "1_1") (pintype "passive"))
      (node (ref "C37") (pin "1") (pinfunction "1_1") (pintype "passive"))
      (node (ref "L3") (pin "1") (pinfunction "1_1") (pintype "passive"))
      (node (ref "PAD1") (pin "1") (pinfunction "P_1") (pintype "passive"))
      (node (ref "R31") (pin "1") (pinfunction "1_1") (pintype "passive"))
      (node (ref "U$3") (pin "3") (pinfunction "VBAT_3") (pintype "bidirectional"))
      (node (ref "U$5") (pin "3") (pinfunction "IN_3") (pintype "bidirectional"))
      (node (ref "U$5") (pin "4") (pinfunction "EN_4") (pintype "bidirectional"))
      (node (ref "U$6") (pin "2") (pinfunction "VIN_2") (pintype "bidirectional"))
      (node (ref "U$6") (pin "3") (pinfunction "EN_3") (pintype "bidirectional"))
    )
    (net (code "42") (name "LOCK_SWITCH") (class "Default")
      (node (ref "S2") (pin "2") (pinfunction "P_2") (pintype "passive"))
      (node (ref "U$2") (pin "PA1") (pinfunction "PA1_PA1") (pintype "bidirectional"))
    )
    (net (code "43") (name "LOUT") (class "Default")
      (node (ref "C23") (pin "+") (pinfunction "+_+") (pintype "passive"))
      (node (ref "U$1") (pin "P$9") (pinfunction "LHPOUT_P$9") (pintype "output"))
    )
    (net (code "44") (name "NRST") (class "Default")
      (node (ref "C46") (pin "1") (pinfunction "1_1") (pintype "passive"))
      (node (ref "JP1") (pin "5") (pinfunction "5_5") (pintype "passive"))
      (node (ref "R35") (pin "1") (pinfunction "1_1") (pintype "passive"))
      (node (ref "U$14") (pin "A") (pinfunction "A_A") (pintype "bidirectional"))
      (node (ref "U$2") (pin "NRST") (pinfunction "NRST_NRST") (pintype "bidirectional"))
    )
    (net (code "45") (name "Net-(C23-Pad-)") (class "Default")
      (node (ref "C23") (pin "-") (pinfunction "-_-") (pintype "passive"))
      (node (ref "J1") (pin "TIP") (pinfunction "TIP_TIP") (pintype "bidirectional"))
      (node (ref "R17") (pin "2") (pinfunction "2_2") (pintype "passive"))
    )
    (net (code "46") (name "Net-(C24-Pad-)") (class "Default")
      (node (ref "C24") (pin "-") (pinfunction "-_-") (pintype "passive"))
      (node (ref "J1") (pin "RING1") (pinfunction "RING1_RING1") (pintype "bidirectional"))
      (node (ref "R18") (pin "2") (pinfunction "2_2") (pintype "passive"))
    )
    (net (code "47") (name "Net-(C25-Pad1)") (class "Default")
      (node (ref "C25") (pin "1") (pinfunction "1_1") (pintype "passive"))
      (node (ref "C26") (pin "2") (pinfunction "2_2") (pintype "passive"))
      (node (ref "J1") (pin "RING2") (pinfunction "RING2_RING2") (pintype "bidirectional"))
      (node (ref "R25") (pin "2") (pinfunction "2_2") (pintype "passive"))
      (node (ref "R26") (pin "1") (pinfunction "1_1") (pintype "passive"))
    )
    (net (code "48") (name "Net-(C40-Pad1)") (class "Default")
      (node (ref "C40") (pin "1") (pinfunction "1_1") (pintype "passive"))
      (node (ref "C47") (pin "1") (pinfunction "1_1") (pintype "passive"))
      (node (ref "R33") (pin "2") (pinfunction "2_2") (pintype "passive"))
      (node (ref "U$2") (pin "VDDA") (pinfunction "VDDA_VDDA") (pintype "bidirectional"))
      (node (ref "U$2") (pin "VREF+") (pinfunction "VREF+_VREF+") (pintype "bidirectional"))
    )
    (net (code "49") (name "Net-(C44-Pad1)") (class "Default")
      (node (ref "C44") (pin "1") (pinfunction "1_1") (pintype "passive"))
      (node (ref "U$2") (pin "VBAT") (pinfunction "VBAT_VBAT") (pintype "bidirectional"))
    )
    (net (code "50") (name "Net-(IC1-I{slash}O_1)") (class "Default")
      (node (ref "IC1") (pin "1") (pinfunction "I/O_1_1") (pintype "bidirectional"))
      (node (ref "X2") (pin "D-") (pinfunction "D-_D-") (pintype "bidirectional"))
    )
    (net (code "51") (name "Net-(IC1-I{slash}O_2)") (class "Default")
      (node (ref "IC1") (pin "3") (pinfunction "I/O_2_3") (pintype "bidirectional"))
      (node (ref "X2") (pin "D+") (pinfunction "D+_D+") (pintype "bidirectional"))
    )
    (net (code "52") (name "Net-(JP2-Pad20)") (class "Default")
      (node (ref "JP2") (pin "20") (pinfunction "20_20") (pintype "passive"))
      (node (ref "R4") (pin "1") (pinfunction "1_1") (pintype "passive"))
    )
    (net (code "53") (name "Net-(JP2-Pad37)") (class "Default")
      (node (ref "JP2") (pin "37") (pinfunction "37_37") (pintype "passive"))
      (node (ref "T1") (pin "C") (pinfunction "C_C") (pintype "passive"))
    )
    (net (code "54") (name "Net-(JP5-VCC)") (class "Default")
      (node (ref "F3") (pin "2") (pinfunction "2_2") (pintype "passive"))
      (node (ref "JP5") (pin "VBUS1") (pinfunction "VCC_VBUS1") (pintype "bidirectional"))
    )
    (net (code "55") (name "Net-(LED1-PadC)") (class "Default")
      (node (ref "LED1") (pin "C") (pinfunction "C_C") (pintype "passive"))
      (node (ref "R20") (pin "1") (pinfunction "1_1") (pintype "passive"))
    )
    (net (code "56") (name "Net-(R1-Pad2)") (class "Default")
      (node (ref "R1") (pin "2") (pinfunction "2_2") (pintype "passive"))
      (node (ref "U$2") (pin "PC10") (pinfunction "PC10_PC10") (pintype "bidirectional"))
    )
    (net (code "57") (name "Net-(R2-Pad2)") (class "Default")
      (node (ref "R2") (pin "2") (pinfunction "2_2") (pintype "passive"))
      (node (ref "U$2") (pin "PC11") (pinfunction "PC11_PC11") (pintype "bidirectional"))
    )
    (net (code "58") (name "Net-(R5-Pad1)") (class "Default")
      (node (ref "R5") (pin "1") (pinfunction "1_1") (pintype "passive"))
      (node (ref "U$2") (pin "PD11") (pinfunction "PD11_PD11") (pintype "bidirectional"))
    )
    (net (code "59") (name "Net-(R12-Pad1)") (class "Default")
      (node (ref "R12") (pin "1") (pinfunction "1_1") (pintype "passive"))
      (node (ref "T1") (pin "B") (pinfunction "B_B") (pintype "passive"))
    )
    (net (code "60") (name "Net-(R13-Pad1)") (class "Default")
      (node (ref "R13") (pin "1") (pinfunction "1_1") (pintype "passive"))
      (node (ref "U$2") (pin "PB5") (pinfunction "PB5_PB5") (pintype "bidirectional"))
    )
    (net (code "61") (name "Net-(R14-Pad1)") (class "Default")
      (node (ref "R14") (pin "1") (pinfunction "1_1") (pintype "passive"))
      (node (ref "R16") (pin "1") (pinfunction "1_1") (pintype "passive"))
      (node (ref "U$2") (pin "PB7") (pinfunction "PB7_PB7") (pintype "bidirectional"))
    )
    (net (code "62") (name "Net-(U$1-VMID)") (class "Default")
      (node (ref "C13") (pin "1") (pinfunction "1_1") (pintype "passive"))
      (node (ref "C14") (pin "+") (pinfunction "+_+") (pintype "passive"))
      (node (ref "U$1") (pin "P$16") (pinfunction "VMID_P$16") (pintype "output"))
    )
    (net (code "63") (name "Net-(U$2-VCAP_1)") (class "Default")
      (node (ref "C3") (pin "1") (pinfunction "1_1") (pintype "passive"))
      (node (ref "U$2") (pin "VCAP1") (pinfunction "VCAP_1_VCAP1") (pintype "bidirectional"))
    )
    (net (code "64") (name "Net-(U$2-VCAP_2)") (class "Default")
      (node (ref "C4") (pin "1") (pinfunction "1_1") (pintype "passive"))
      (node (ref "U$2") (pin "VCAP2") (pinfunction "VCAP_2_VCAP2") (pintype "bidirectional"))
    )
    (net (code "65") (name "Net-(U$3-PROG)") (class "Default")
      (node (ref "R19") (pin "1") (pinfunction "1_1") (pintype "passive"))
      (node (ref "U$3") (pin "5") (pinfunction "PROG_5") (pintype "bidirectional"))
    )
    (net (code "66") (name "Net-(U$3-STAT)") (class "Default")
      (node (ref "R20") (pin "2") (pinfunction "2_2") (pintype "passive"))
      (node (ref "R30") (pin "2") (pinfunction "2_2") (pintype "passive"))
      (node (ref "U$3") (pin "1") (pinfunction "STAT_1") (pintype "bidirectional"))
    )
    (net (code "67") (name "Net-(U$3-VDD)") (class "Default")
      (node (ref "C28") (pin "1") (pinfunction "1_1") (pintype "passive"))
      (node (ref "F3") (pin "1") (pinfunction "1_1") (pintype "passive"))
      (node (ref "LED1") (pin "A") (pinfunction "A_A") (pintype "passive"))
      (node (ref "U$3") (pin "4") (pinfunction "VDD_4") (pintype "bidirectional"))
    )
    (net (code "68") (name "Net-(U$5-AUX)") (class "Default")
      (node (ref "C31") (pin "1") (pinfunction "1_1") (pintype "passive"))
      (node (ref "U$5") (pin "10") (pinfunction "AUX_10") (pintype "bidirectional"))
    )
    (net (code "69") (name "Net-(U$5-ENUSB)") (class "Default")
      (node (ref "R23") (pin "1") (pinfunction "1_1") (pintype "passive"))
      (node (ref "R29") (pin "1") (pinfunction "1_1") (pintype "passive"))
      (node (ref "U$5") (pin "7") (pinfunction "ENUSB_7") (pintype "bidirectional"))
    )
    (net (code "70") (name "Net-(U$5-ILIM)") (class "Default")
      (node (ref "R21") (pin "2") (pinfunction "2_2") (pintype "passive"))
      (node (ref "U$5") (pin "6") (pinfunction "ILIM_6") (pintype "bidirectional"))
    )
    (net (code "71") (name "Net-(U$5-SW)") (class "Default")
      (node (ref "L3") (pin "2") (pinfunction "2_2") (pintype "passive"))
      (node (ref "U$5") (pin "1") (pinfunction "SW_1") (pintype "bidirectional"))
    )
    (net (code "72") (name "Net-(U$5-~{FAULT})") (class "Default")
      (node (ref "R22") (pin "1") (pinfunction "1_1") (pintype "passive"))
      (node (ref "U$5") (pin "8") (pinfunction "~{FAULT}_8") (pintype "bidirectional"))
    )
    (net (code "73") (name "Net-(U$6-FB)") (class "Default")
      (node (ref "C39") (pin "1") (pinfunction "1_1") (pintype "passive"))
      (node (ref "R24") (pin "2") (pinfunction "2_2") (pintype "passive"))
      (node (ref "R27") (pin "1") (pinfunction "1_1") (pintype "passive"))
      (node (ref "U$6") (pin "8") (pinfunction "FB_8") (pintype "bidirectional"))
    )
    (net (code "74") (name "Net-(U$6-L1)") (class "Default")
      (node (ref "L2") (pin "1") (pinfunction "1_1") (pintype "passive"))
      (node (ref "U$6") (pin "1") (pinfunction "L1_1") (pintype "bidirectional"))
    )
    (net (code "75") (name "Net-(U$6-L2)") (class "Default")
      (node (ref "L2") (pin "2") (pinfunction "2_2") (pintype "passive"))
      (node (ref "U$6") (pin "10") (pinfunction "L2_10") (pintype "bidirectional"))
    )
    (net (code "76") (name "Net-(U$6-VAUX)") (class "Default")
      (node (ref "C38") (pin "1") (pinfunction "1_1") (pintype "passive"))
      (node (ref "U$6") (pin "6") (pinfunction "VAUX_6") (pintype "bidirectional"))
    )
    (net (code "77") (name "OSC32_IN") (class "Default")
      (node (ref "C1") (pin "2") (pinfunction "2_2") (pintype "passive"))
      (node (ref "U$2") (pin "PC14") (pinfunction "PC14_PC14") (pintype "bidirectional"))
      (node (ref "X1") (pin "1") (pinfunction "1_1") (pintype "passive"))
    )
    (net (code "78") (name "OSC32_OUT") (class "Default")
      (node (ref "C2") (pin "2") (pinfunction "2_2") (pintype "passive"))
      (node (ref "U$2") (pin "PC15") (pinfunction "PC15_PC15") (pintype "bidirectional"))
      (node (ref "X1") (pin "2") (pinfunction "2_2") (pintype "passive"))
    )
    (net (code "79") (name "PH0") (class "Default")
      (node (ref "U$2") (pin "PH0") (pinfunction "PH0_PH0") (pintype "bidirectional"))
      (node (ref "U$7") (pin "3") (pinfunction "OUT_3") (pintype "output"))
    )
    (net (code "80") (name "PH1") (class "Default")
      (node (ref "U$2") (pin "PH1") (pinfunction "PH1_PH1") (pintype "bidirectional"))
    )
    (net (code "81") (name "PWR_BTN") (class "Default")
      (node (ref "U$2") (pin "PB10") (pinfunction "PB10_PB10") (pintype "bidirectional"))
      (node (ref "U$8") (pin "A") (pinfunction "A_A") (pintype "bidirectional"))
    )
    (net (code "82") (name "REST") (class "Default")
      (node (ref "JP2") (pin "33") (pinfunction "33_33") (pintype "passive"))
      (node (ref "U$2") (pin "PD13") (pinfunction "PD13_PD13") (pintype "bidirectional"))
    )
    (net (code "83") (name "ROUT") (class "Default")
      (node (ref "C24") (pin "+") (pinfunction "+_+") (pintype "passive"))
      (node (ref "U$1") (pin "P$10") (pinfunction "RHPOUT_P$10") (pintype "output"))
    )
    (net (code "84") (name "SDIO_CD") (class "Default")
      (node (ref "R10") (pin "1") (pinfunction "1_1") (pintype "passive"))
      (node (ref "U$2") (pin "PD3") (pinfunction "PD3_PD3") (pintype "bidirectional"))
      (node (ref "U1") (pin "CD1") (pinfunction "SHIELD_CD1") (pintype "bidirectional"))
    )
    (net (code "85") (name "SDIO_CLK") (class "Default")
      (node (ref "R9") (pin "1") (pinfunction "1_1") (pintype "passive"))
      (node (ref "U$2") (pin "PC12") (pinfunction "PC12_PC12") (pintype "bidirectional"))
      (node (ref "U1") (pin "5") (pinfunction "SCK_5") (pintype "bidirectional"))
    )
    (net (code "86") (name "SDIO_CMD") (class "Default")
      (node (ref "R11") (pin "1") (pinfunction "1_1") (pintype "passive"))
      (node (ref "U$2") (pin "PD2") (pinfunction "PD2_PD2") (pintype "bidirectional"))
      (node (ref "U1") (pin "3") (pinfunction "DI_3") (pintype "bidirectional"))
    )
    (net (code "87") (name "SDIO_D0") (class "Default")
      (node (ref "R3") (pin "1") (pinfunction "1_1") (pintype "passive"))
      (node (ref "U$2") (pin "PC8") (pinfunction "PC8_PC8") (pintype "bidirectional"))
      (node (ref "U1") (pin "7") (pinfunction "DO_7") (pintype "bidirectional"))
    )
    (net (code "88") (name "SDIO_D1") (class "Default")
      (node (ref "R6") (pin "1") (pinfunction "1_1") (pintype "passive"))
      (node (ref "U$2") (pin "PC9") (pinfunction "PC9_PC9") (pintype "bidirectional"))
      (node (ref "U1") (pin "8") (pinfunction "RSV_8") (pintype "bidirectional"))
    )
    (net (code "89") (name "SDIO_D2") (class "Default")
      (node (ref "R1") (pin "1") (pinfunction "1_1") (pintype "passive"))
      (node (ref "R7") (pin "1") (pinfunction "1_1") (pintype "passive"))
      (node (ref "U1") (pin "1") (pinfunction "NC_1") (pintype "bidirectional"))
    )
    (net (code "90") (name "SDIO_D3") (class "Default")
      (node (ref "R2") (pin "1") (pinfunction "1_1") (pintype "passive"))
      (node (ref "R8") (pin "1") (pinfunction "1_1") (pintype "passive"))
      (node (ref "U1") (pin "2") (pinfunction "CS_2") (pintype "bidirectional"))
    )
    (net (code "91") (name "SD_CLK") (class "Default")
      (node (ref "JP2") (pin "32") (pinfunction "32_32") (pintype "passive"))
      (node (ref "U$2") (pin "PA5") (pinfunction "PA5_PA5") (pintype "bidirectional"))
    )
    (net (code "92") (name "SD_CS") (class "Default")
      (node (ref "JP2") (pin "36") (pinfunction "36_36") (pintype "passive"))
      (node (ref "R36") (pin "2") (pinfunction "2_2") (pintype "passive"))
      (node (ref "U$2") (pin "PA4") (pinfunction "PA4_PA4") (pintype "bidirectional"))
    )
    (net (code "93") (name "SD_DIN") (class "Default")
      (node (ref "JP2") (pin "34") (pinfunction "34_34") (pintype "passive"))
      (node (ref "U$2") (pin "PA7") (pinfunction "PA7_PA7") (pintype "bidirectional"))
    )
    (net (code "94") (name "SD_DO") (class "Default")
      (node (ref "JP2") (pin "30") (pinfunction "30_30") (pintype "passive"))
      (node (ref "U$2") (pin "PA6") (pinfunction "PA6_PA6") (pintype "bidirectional"))
    )
    (net (code "95") (name "SW2") (class "Default")
      (node (ref "U$2") (pin "PB9") (pinfunction "PB9_PB9") (pintype "bidirectional"))
      (node (ref "U$4") (pin "SW2") (pinfunction "SW2_SW2") (pintype "bidirectional"))
    )
    (net (code "96") (name "SWD_CLK") (class "Default")
      (node (ref "JP1") (pin "2") (pinfunction "2_2") (pintype "passive"))
      (node (ref "U$2") (pin "PA14") (pinfunction "PA14_PA14") (pintype "bidirectional"))
    )
    (net (code "97") (name "SWD_IO") (class "Default")
      (node (ref "JP1") (pin "4") (pinfunction "4_4") (pintype "passive"))
      (node (ref "U$2") (pin "PA13") (pinfunction "PA13_PA13") (pintype "bidirectional"))
    )
    (net (code "98") (name "SW_A") (class "Default")
      (node (ref "U$2") (pin "PE3") (pinfunction "PE3_PE3") (pintype "bidirectional"))
      (node (ref "U$4") (pin "A") (pinfunction "A_A") (pintype "bidirectional"))
    )
    (net (code "99") (name "SW_B") (class "Default")
      (node (ref "U$2") (pin "PB8") (pinfunction "PB8_PB8") (pintype "bidirectional"))
      (node (ref "U$4") (pin "B") (pinfunction "B_B") (pintype "bidirectional"))
    )
    (net (code "100") (name "T_CLK") (class "Default")
      (node (ref "JP2") (pin "18") (pinfunction "18_18") (pintype "passive"))
      (node (ref "U$2") (pin "PB13") (pinfunction "PB13_PB13") (pintype "bidirectional"))
    )
    (net (code "101") (name "T_CS") (class "Default")
      (node (ref "R37") (pin "2") (pinfunction "2_2") (pintype "passive"))
      (node (ref "R4") (pin "2") (pinfunction "2_2") (pintype "passive"))
      (node (ref "U$2") (pin "PB12") (pinfunction "PB12_PB12") (pintype "bidirectional"))
    )
    (net (code "102") (name "T_DIN") (class "Default")
      (node (ref "JP2") (pin "22") (pinfunction "22_22") (pintype "passive"))
      (node (ref "U$2") (pin "PB15") (pinfunction "PB15_PB15") (pintype "bidirectional"))
    )
    (net (code "103") (name "T_DO") (class "Default")
      (node (ref "JP2") (pin "26") (pinfunction "26_26") (pintype "passive"))
      (node (ref "U$2") (pin "PB14") (pinfunction "PB14_PB14") (pintype "bidirectional"))
    )
    (net (code "104") (name "T_IRQ") (class "Default")
      (node (ref "JP2") (pin "28") (pinfunction "28_28") (pintype "passive"))
      (node (ref "U$2") (pin "PD12") (pinfunction "PD12_PD12") (pintype "bidirectional"))
    )
    (net (code "105") (name "UART1_TX") (class "Default")
      (node (ref "JP1") (pin "6") (pinfunction "6_6") (pintype "passive"))
      (node (ref "U$2") (pin "PA9") (pinfunction "PA9_PA9") (pintype "bidirectional"))
    )
    (net (code "106") (name "USBFAULT_CPU") (class "Default")
      (node (ref "R23") (pin "2") (pinfunction "2_2") (pintype "passive"))
      (node (ref "U$2") (pin "PA8") (pinfunction "PA8_PA8") (pintype "bidirectional"))
    )
    (net (code "107") (name "USB_D_N") (class "Default")
      (node (ref "IC1") (pin "6") (pinfunction "I/O1_6") (pintype "bidirectional"))
      (node (ref "U$2") (pin "PA11") (pinfunction "PA11_PA11") (pintype "bidirectional"))
    )
    (net (code "108") (name "USB_D_P") (class "Default")
      (node (ref "IC1") (pin "4") (pinfunction "I/O2_4") (pintype "bidirectional"))
      (node (ref "U$2") (pin "PA12") (pinfunction "PA12_PA12") (pintype "bidirectional"))
    )
    (net (code "109") (name "VOL_DN") (class "Default")
      (node (ref "U$10") (pin "A") (pinfunction "A_A") (pintype "bidirectional"))
      (node (ref "U$2") (pin "PE2") (pinfunction "PE2_PE2") (pintype "bidirectional"))
    )
    (net (code "110") (name "VOL_UP") (class "Default")
      (node (ref "U$2") (pin "PE0") (pinfunction "PE0_PE0") (pintype "bidirectional"))
      (node (ref "U$9") (pin "A") (pinfunction "A_A") (pintype "bidirectional"))
    )
    (net (code "111") (name "XTI") (class "Default")
      (node (ref "C11") (pin "1") (pinfunction "1_1") (pintype "passive"))
      (node (ref "U$1") (pin "P$25") (pinfunction "XTI/MCLK_P$25") (pintype "input"))
      (node (ref "Y2") (pin "3") (pinfunction "1_3") (pintype "passive"))
    )
    (net (code "112") (name "XTO") (class "Default")
      (node (ref "C12") (pin "1") (pinfunction "1_1") (pintype "passive"))
      (node (ref "U$1") (pin "P$26") (pinfunction "XTO_P$26") (pintype "output"))
      (node (ref "Y2") (pin "1") (pinfunction "2_1") (pintype "passive"))
    )
    (net (code "113") (name "_5V") (class "Default")
      (node (ref "C29") (pin "1") (pinfunction "1_1") (pintype "passive"))
      (node (ref "C30") (pin "+") (pinfunction "+_+") (pintype "passive"))
      (node (ref "IC1") (pin "5") (pinfunction "VBUS_5") (pintype "bidirectional"))
      (node (ref "U$5") (pin "9") (pinfunction "USB_9") (pintype "bidirectional"))
      (node (ref "X2") (pin "VBUS") (pinfunction "VBUS_VBUS") (pintype "bidirectional"))
    )
    (net (code "114") (name "unconnected-(JP2-Pad5)") (class "Default")
      (node (ref "JP2") (pin "5") (pinfunction "5_5") (pintype "passive"))
    )
    (net (code "115") (name "unconnected-(JP2-Pad24)") (class "Default")
      (node (ref "JP2") (pin "24") (pinfunction "24_24") (pintype "passive"))
    )
    (net (code "116") (name "unconnected-(JP2-Pad35)") (class "Default")
      (node (ref "JP2") (pin "35") (pinfunction "35_35") (pintype "passive"))
    )
    (net (code "117") (name "unconnected-(JP2-Pad38)") (class "Default")
      (node (ref "JP2") (pin "38") (pinfunction "38_38") (pintype "passive"))
    )
    (net (code "118") (name "unconnected-(JP2-Pad39)") (class "Default")
      (node (ref "JP2") (pin "39") (pinfunction "39_39") (pintype "passive"))
    )
    (net (code "119") (name "unconnected-(JP2-Pad40)") (class "Default")
      (node (ref "JP2") (pin "40") (pinfunction "40_40") (pintype "passive"))
    )
    (net (code "120") (name "unconnected-(JP5-D+-PadD+1)") (class "Default")
      (node (ref "JP5") (pin "D+1") (pinfunction "D+_D+1") (pintype "bidirectional"))
    )
    (net (code "121") (name "unconnected-(JP5-D--PadD-1)") (class "Default")
      (node (ref "JP5") (pin "D-1") (pinfunction "D-_D-1") (pintype "bidirectional"))
    )
    (net (code "122") (name "unconnected-(JP5-ID-PadID1)") (class "Default")
      (node (ref "JP5") (pin "ID1") (pinfunction "ID_ID1") (pintype "bidirectional"))
    )
    (net (code "123") (name "unconnected-(S2-O-Pad1)") (class "Default")
      (node (ref "S2") (pin "1") (pinfunction "O_1") (pintype "passive"))
    )
    (net (code "124") (name "unconnected-(U$1-CLKOUT-PadP$2)") (class "Default")
      (node (ref "U$1") (pin "P$2") (pinfunction "CLKOUT_P$2") (pintype "output"))
    )
    (net (code "125") (name "unconnected-(U$1-LLINEIN-PadP$20)") (class "Default")
      (node (ref "U$1") (pin "P$20") (pinfunction "LLINEIN_P$20") (pintype "input"))
    )
    (net (code "126") (name "unconnected-(U$1-LOUT-PadP$12)") (class "Default")
      (node (ref "U$1") (pin "P$12") (pinfunction "LOUT_P$12") (pintype "output"))
    )
    (net (code "127") (name "unconnected-(U$1-RLINEIN-PadP$19)") (class "Default")
      (node (ref "U$1") (pin "P$19") (pinfunction "RLINEIN_P$19") (pintype "input"))
    )
    (net (code "128") (name "unconnected-(U$1-ROUT-PadP$13)") (class "Default")
      (node (ref "U$1") (pin "P$13") (pinfunction "ROUT_P$13") (pintype "output"))
    )
    (net (code "129") (name "unconnected-(U$2-PadPA3)") (class "Default")
      (node (ref "U$2") (pin "PA3") (pinfunction "PA3_PA3") (pintype "bidirectional"))
    )
    (net (code "130") (name "unconnected-(U$2-PadPB0)") (class "Default")
      (node (ref "U$2") (pin "PB0") (pinfunction "PB0_PB0") (pintype "bidirectional"))
    )
    (net (code "131") (name "unconnected-(U$2-PadPB1)") (class "Default")
      (node (ref "U$2") (pin "PB1") (pinfunction "PB1_PB1") (pintype "bidirectional"))
    )
    (net (code "132") (name "unconnected-(U$2-PadPB2)") (class "Default")
      (node (ref "U$2") (pin "PB2") (pinfunction "PB2_PB2") (pintype "bidirectional"))
    )
    (net (code "133") (name "unconnected-(U$2-PadPB11)") (class "Default")
      (node (ref "U$2") (pin "PB11") (pinfunction "PB11_PB11") (pintype "bidirectional"))
    )
    (net (code "134") (name "unconnected-(U$2-PadPC0)") (class "Default")
      (node (ref "U$2") (pin "PC0") (pinfunction "PC0_PC0") (pintype "bidirectional"))
    )
    (net (code "135") (name "unconnected-(U$2-PadPC1)") (class "Default")
      (node (ref "U$2") (pin "PC1") (pinfunction "PC1_PC1") (pintype "bidirectional"))
    )
    (net (code "136") (name "unconnected-(U$2-PadPC4)") (class "Default")
      (node (ref "U$2") (pin "PC4") (pinfunction "PC4_PC4") (pintype "bidirectional"))
    )
    (net (code "137") (name "unconnected-(U$2-PadPC5)") (class "Default")
      (node (ref "U$2") (pin "PC5") (pinfunction "PC5_PC5") (pintype "bidirectional"))
    )
    (net (code "138") (name "unconnected-(U$2-PadPC13)") (class "Default")
      (node (ref "U$2") (pin "PC13") (pinfunction "PC13_PC13") (pintype "bidirectional"))
    )
    (net (code "139") (name "unconnected-(U$2-PadPD6)") (class "Default")
      (node (ref "U$2") (pin "PD6") (pinfunction "PD6_PD6") (pintype "bidirectional"))
    )
    (net (code "140") (name "unconnected-(U$2-PadPE1)") (class "Default")
      (node (ref "U$2") (pin "PE1") (pinfunction "PE1_PE1") (pintype "bidirectional"))
    )
    (net (code "141") (name "unconnected-(U$2-PadPE4)") (class "Default")
      (node (ref "U$2") (pin "PE4") (pinfunction "PE4_PE4") (pintype "bidirectional"))
    )
    (net (code "142") (name "unconnected-(U$2-PadPE5)") (class "Default")
      (node (ref "U$2") (pin "PE5") (pinfunction "PE5_PE5") (pintype "bidirectional"))
    )
    (net (code "143") (name "unconnected-(U$2-PadPE6)") (class "Default")
      (node (ref "U$2") (pin "PE6") (pinfunction "PE6_PE6") (pintype "bidirectional"))
    )
    (net (code "144") (name "unconnected-(U$6-PG-Pad5)") (class "Default")
      (node (ref "U$6") (pin "5") (pinfunction "PG_5") (pintype "bidirectional"))
    )
    (net (code "145") (name "unconnected-(U$7-TRI-Pad1)") (class "Default")
      (node (ref "U$7") (pin "1") (pinfunction "TRI_1") (pintype "input"))
    )
  )
)
